# gpio_led.net
KiCad netlist of a schematic drawn in Altium Designer
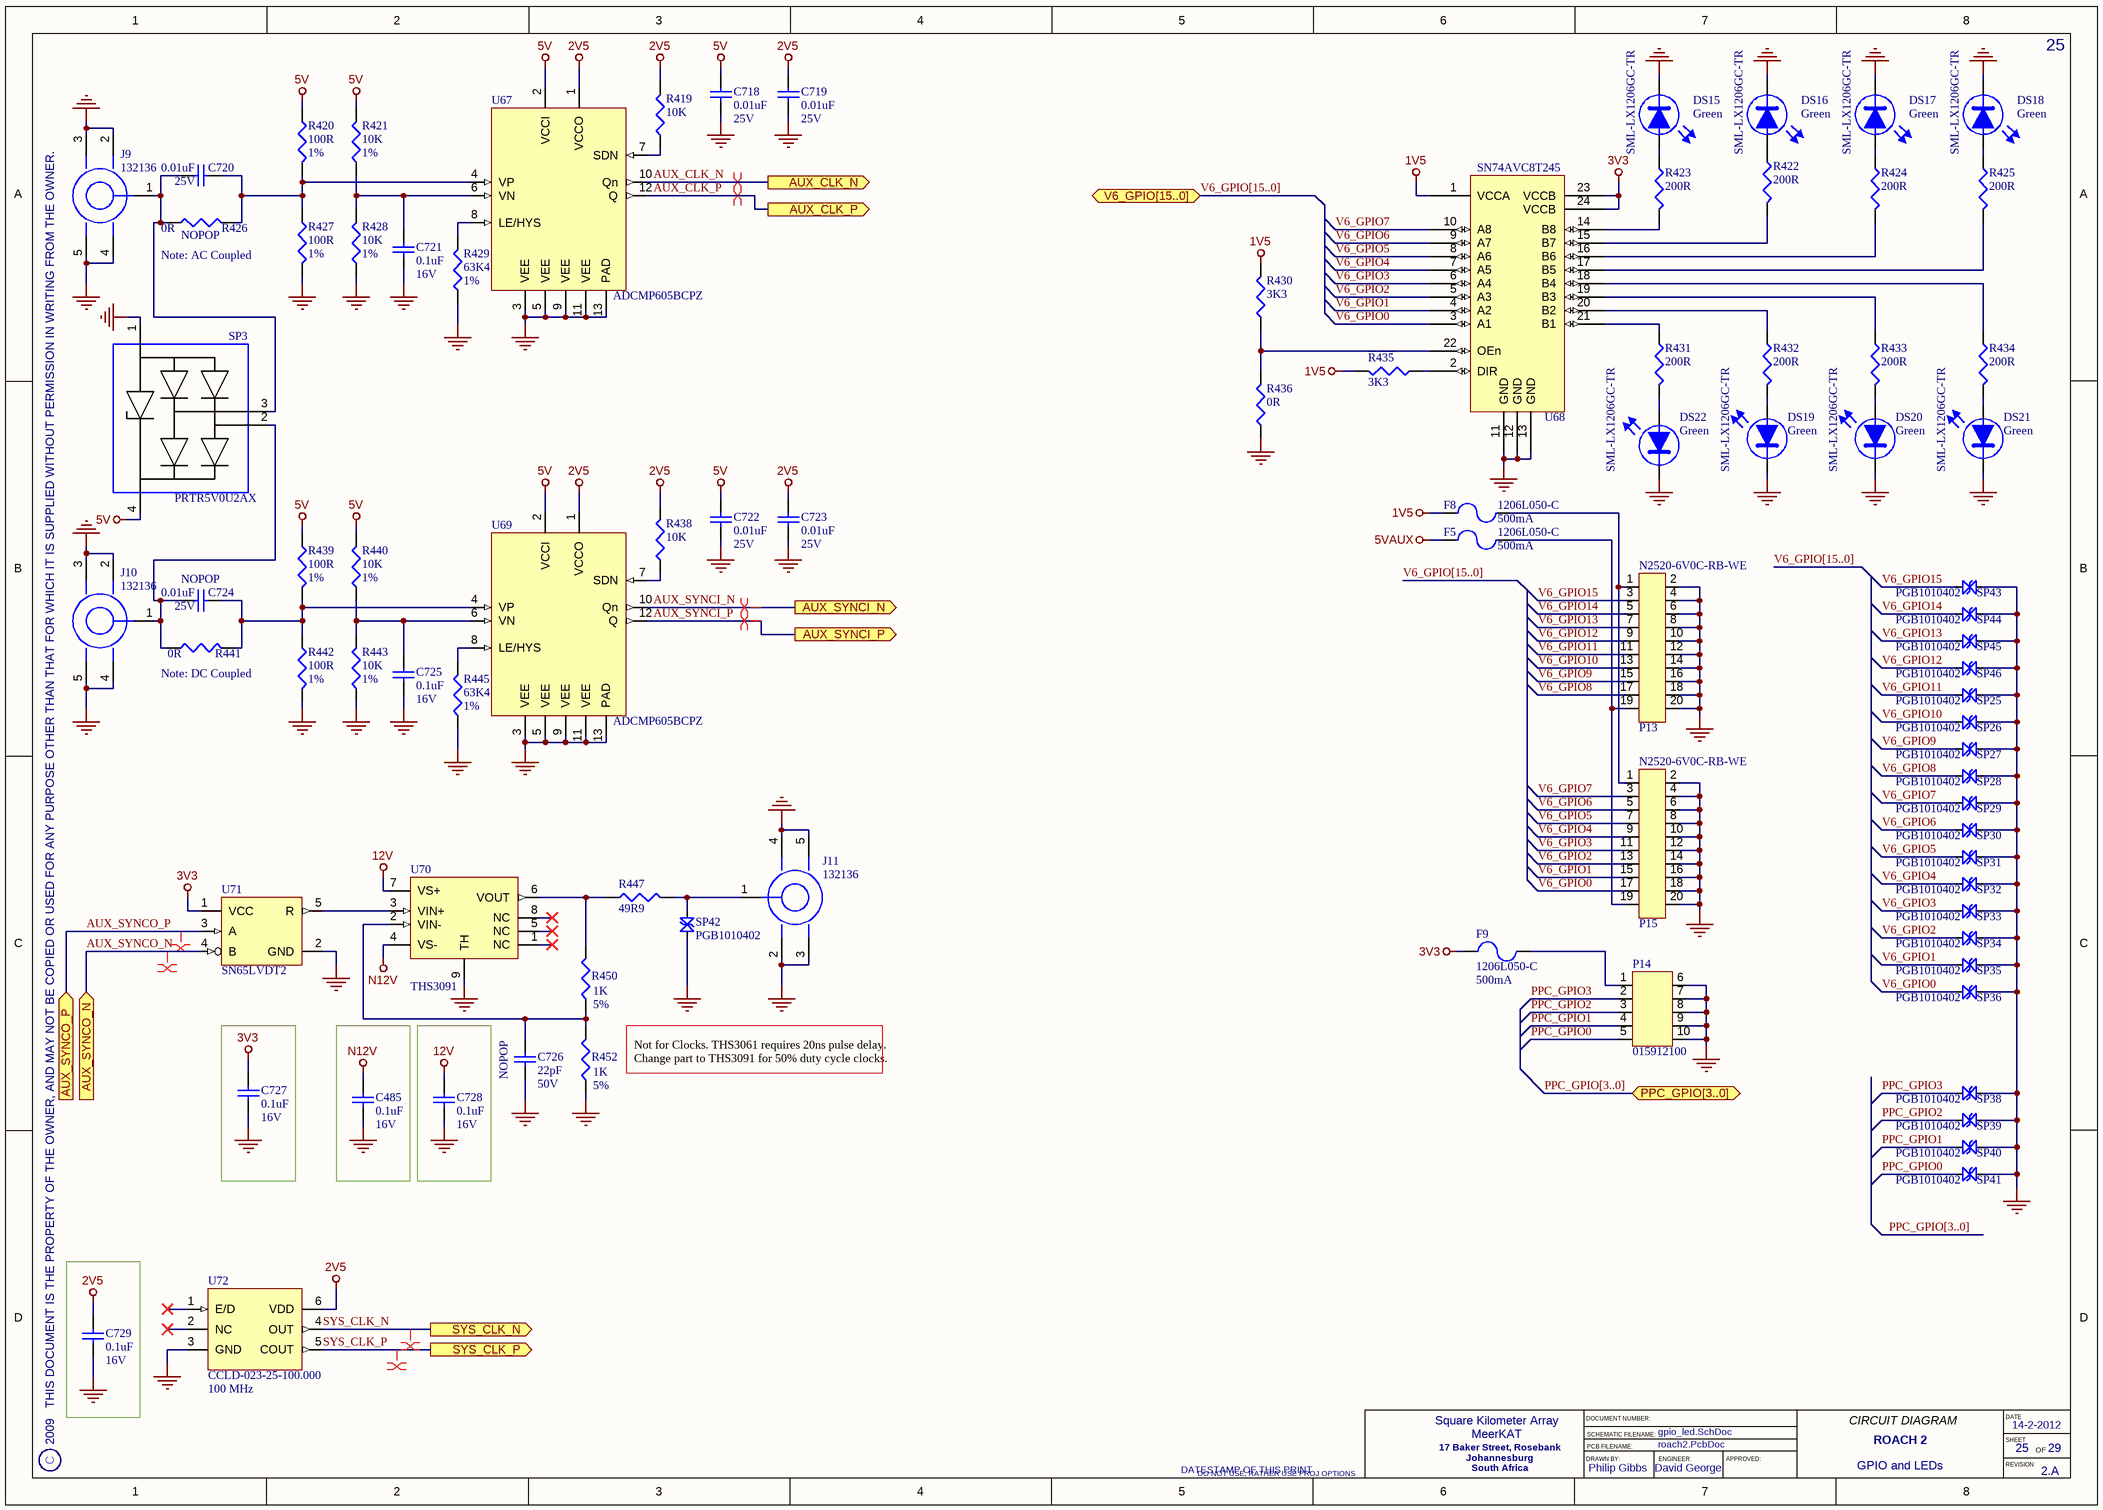
[diagram p0: gpio_led.SchDoc]

(export (version "E")
  (design (tool "Eeschema 10.0.6"))
  (components
    (comp (ref "C485")
      (value "0.1uF")
      (footprint "CAPC1005X60L")
      (description "0.1uF, Ceramic Capacitor")
      (fields
        (field (name "RATING") "16V")
        (field (name "MANUFACTURER") "VENKEL")
        (field (name "PARTNUM") "C0402X7R160-104KN")
      )
      (libsource (lib "altium_db") (part "CapStd"))
    )
    (comp (ref "C718")
      (value "0.01uF")
      (footprint "CAPC1005X55L")
      (description "0.01uF, Ceramic Capacitor")
      (fields
        (field (name "RATING") "25V")
        (field (name "MANUFACTURER") "MURATA")
        (field (name "PARTNUM") "GRM155R71E103KA01D")
      )
      (libsource (lib "altium_db") (part "CapStd"))
    )
    (comp (ref "C719")
      (value "0.01uF")
      (footprint "CAPC1005X55L")
      (description "0.01uF, Ceramic Capacitor")
      (fields
        (field (name "RATING") "25V")
        (field (name "MANUFACTURER") "MURATA")
        (field (name "PARTNUM") "GRM155R71E103KA01D")
      )
      (libsource (lib "altium_db") (part "CapStd"))
    )
    (comp (ref "C720")
      (value "0.01uF")
      (footprint "CAPC1005X55L")
      (description "0.01uF, Ceramic Capacitor")
      (fields
        (field (name "RATING") "25V")
        (field (name "MANUFACTURER") "MURATA")
        (field (name "PARTNUM") "GRM155R71E103KA01D")
      )
      (libsource (lib "altium_db") (part "CapStd"))
    )
    (comp (ref "C721")
      (value "0.1uF")
      (footprint "CAPC1005X60L")
      (description "0.1uF, Ceramic Capacitor")
      (fields
        (field (name "RATING") "16V")
        (field (name "MANUFACTURER") "VENKEL")
        (field (name "PARTNUM") "C0402X7R160-104KN")
      )
      (libsource (lib "altium_db") (part "CapStd"))
    )
    (comp (ref "C722")
      (value "0.01uF")
      (footprint "CAPC1005X55L")
      (description "0.01uF, Ceramic Capacitor")
      (fields
        (field (name "RATING") "25V")
        (field (name "MANUFACTURER") "MURATA")
        (field (name "PARTNUM") "GRM155R71E103KA01D")
      )
      (libsource (lib "altium_db") (part "CapStd"))
    )
    (comp (ref "C723")
      (value "0.01uF")
      (footprint "CAPC1005X55L")
      (description "0.01uF, Ceramic Capacitor")
      (fields
        (field (name "RATING") "25V")
        (field (name "MANUFACTURER") "MURATA")
        (field (name "PARTNUM") "GRM155R71E103KA01D")
      )
      (libsource (lib "altium_db") (part "CapStd"))
    )
    (comp (ref "C724")
      (value "0.01uF")
      (footprint "CAPC1005X55L")
      (description "0.01uF, Ceramic Capacitor")
      (fields
        (field (name "RATING") "25V")
        (field (name "MANUFACTURER") "MURATA")
        (field (name "PARTNUM") "GRM155R71E103KA01D")
      )
      (libsource (lib "altium_db") (part "CapStd"))
    )
    (comp (ref "C725")
      (value "0.1uF")
      (footprint "CAPC1005X60L")
      (description "0.1uF, Ceramic Capacitor")
      (fields
        (field (name "RATING") "16V")
        (field (name "MANUFACTURER") "VENKEL")
        (field (name "PARTNUM") "C0402X7R160-104KN")
      )
      (libsource (lib "altium_db") (part "CapStd"))
    )
    (comp (ref "C726")
      (value "22pF")
      (footprint "CAPC1005X55L")
      (description "22pF, Ceramic Capacitor")
      (fields
        (field (name "RATING") "50V")
        (field (name "MANUFACTURER") "MURATA")
        (field (name "PARTNUM") "GRM1555C1H220JZ01D")
      )
      (libsource (lib "altium_db") (part "CapStd"))
    )
    (comp (ref "C727")
      (value "0.1uF")
      (footprint "CAPC1005X60L")
      (description "0.1uF, Ceramic Capacitor")
      (fields
        (field (name "RATING") "16V")
        (field (name "MANUFACTURER") "VENKEL")
        (field (name "PARTNUM") "C0402X7R160-104KN")
      )
      (libsource (lib "altium_db") (part "CapStd"))
    )
    (comp (ref "C728")
      (value "0.1uF")
      (footprint "CAPC1005X60L")
      (description "0.1uF, Ceramic Capacitor")
      (fields
        (field (name "RATING") "16V")
        (field (name "MANUFACTURER") "VENKEL")
        (field (name "PARTNUM") "C0402X7R160-104KN")
      )
      (libsource (lib "altium_db") (part "CapStd"))
    )
    (comp (ref "C729")
      (value "0.1uF")
      (footprint "CAPC1005X60L")
      (description "0.1uF, Ceramic Capacitor")
      (fields
        (field (name "RATING") "16V")
        (field (name "MANUFACTURER") "VENKEL")
        (field (name "PARTNUM") "C0402X7R160-104KN")
      )
      (libsource (lib "altium_db") (part "CapStd"))
    )
    (comp (ref "DS15")
      (value "SML-LX1206GC-TR")
      (footprint "LEDC3216X120N")
      (description "Green, Surface mount, LED, 1206")
      (fields (field (name "COLOUR") "Green") (field (name "MANUFACTURER") "LUMEX"))
      (libsource (lib "altium_db") (part "LEDSTD"))
    )
    (comp (ref "DS16")
      (value "SML-LX1206GC-TR")
      (footprint "LEDC3216X120N")
      (description "Green, Surface mount, LED, 1206")
      (fields (field (name "COLOUR") "Green") (field (name "MANUFACTURER") "LUMEX"))
      (libsource (lib "altium_db") (part "LEDSTD"))
    )
    (comp (ref "DS17")
      (value "SML-LX1206GC-TR")
      (footprint "LEDC3216X120N")
      (description "Green, Surface mount, LED, 1206")
      (fields (field (name "COLOUR") "Green") (field (name "MANUFACTURER") "LUMEX"))
      (libsource (lib "altium_db") (part "LEDSTD"))
    )
    (comp (ref "DS18")
      (value "SML-LX1206GC-TR")
      (footprint "LEDC3216X120N")
      (description "Green, Surface mount, LED, 1206")
      (fields (field (name "COLOUR") "Green") (field (name "MANUFACTURER") "LUMEX"))
      (libsource (lib "altium_db") (part "LEDSTD"))
    )
    (comp (ref "DS19")
      (value "SML-LX1206GC-TR")
      (footprint "LEDC3216X120N")
      (description "Green, Surface mount, LED, 1206")
      (fields (field (name "COLOUR") "Green") (field (name "MANUFACTURER") "LUMEX"))
      (libsource (lib "altium_db") (part "LEDSTD"))
    )
    (comp (ref "DS20")
      (value "SML-LX1206GC-TR")
      (footprint "LEDC3216X120N")
      (description "Green, Surface mount, LED, 1206")
      (fields (field (name "COLOUR") "Green") (field (name "MANUFACTURER") "LUMEX"))
      (libsource (lib "altium_db") (part "LEDSTD"))
    )
    (comp (ref "DS21")
      (value "SML-LX1206GC-TR")
      (footprint "LEDC3216X120N")
      (description "Green, Surface mount, LED, 1206")
      (fields (field (name "COLOUR") "Green") (field (name "MANUFACTURER") "LUMEX"))
      (libsource (lib "altium_db") (part "LEDSTD"))
    )
    (comp (ref "DS22")
      (value "SML-LX1206GC-TR")
      (footprint "LEDC3216X120N")
      (description "Green, Surface mount, LED, 1206")
      (fields (field (name "COLOUR") "Green") (field (name "MANUFACTURER") "LUMEX"))
      (libsource (lib "altium_db") (part "LEDSTD"))
    )
    (comp (ref "F5")
      (value "1206L050-C")
      (footprint "FUSMC3215X145")
      (description "Resettable, Surface mount Fuse")
      (fields
        (field (name "PARTNUM") "1206L050-C")
        (field (name "MANUFACTURER") "Littelfuse")
        (field (name "RATING") "500mA")
      )
      (libsource (lib "altium_db") (part "FuseStd"))
    )
    (comp (ref "F8")
      (value "1206L050-C")
      (footprint "FUSMC3215X145")
      (description "Resettable, Surface mount Fuse")
      (fields
        (field (name "PARTNUM") "1206L050-C")
        (field (name "MANUFACTURER") "Littelfuse")
        (field (name "RATING") "500mA")
      )
      (libsource (lib "altium_db") (part "FuseStd"))
    )
    (comp (ref "F9")
      (value "1206L050-C")
      (footprint "FUSMC3215X145")
      (description "Resettable, Surface mount Fuse")
      (fields
        (field (name "PARTNUM") "1206L050-C")
        (field (name "MANUFACTURER") "Littelfuse")
        (field (name "RATING") "500mA")
      )
      (libsource (lib "altium_db") (part "FuseStd"))
    )
    (comp (ref "J9")
      (value "132136")
      (footprint "AMPHENOL_132134")
      (description "PCB-Mounted, Vertical, SMA Connector")
      (fields (field (name "PARTNUM") "132136") (field (name "MANUFACTURER") "Amphenol"))
      (libsource (lib "altium_db") (part "SMA_PCBMOUNT"))
    )
    (comp (ref "J10")
      (value "132136")
      (footprint "AMPHENOL_132134")
      (description "PCB-Mounted, Vertical, SMA Connector")
      (fields (field (name "PARTNUM") "132136") (field (name "MANUFACTURER") "Amphenol"))
      (libsource (lib "altium_db") (part "SMA_PCBMOUNT"))
    )
    (comp (ref "J11")
      (value "132136")
      (footprint "AMPHENOL_132134")
      (description "PCB-Mounted, Vertical, SMA Connector")
      (fields (field (name "PARTNUM") "132136") (field (name "MANUFACTURER") "Amphenol"))
      (libsource (lib "altium_db") (part "SMA_PCBMOUNT"))
    )
    (comp (ref "P13")
      (value "N2520-6V0C-RB-WE")
      (footprint "3M_N2520-6V0C-RB-WE")
      (description "2x10, 2.54mm Pitch, Male Shrouded Header")
      (fields (field (name "PARTNUM") "N2520-6V0C-RB-WE") (field (name "MANUFACTURER") "3M"))
      (libsource (lib "altium_db") (part "con_hdr_2x10_shr"))
    )
    (comp (ref "P14")
      (value "015912100")
      (footprint "MOLEX_0015912100")
      (description "2x5, 2.54 mm Pitch, Male Header")
      (fields (field (name "PARTNUM") "015912100") (field (name "MANUFACTURER") "Molex"))
      (libsource (lib "altium_db") (part "con_hdr_2x5"))
    )
    (comp (ref "P15")
      (value "N2520-6V0C-RB-WE")
      (footprint "3M_N2520-6V0C-RB-WE")
      (description "2x10, 2.54mm Pitch, Male Shrouded Header")
      (fields (field (name "PARTNUM") "N2520-6V0C-RB-WE") (field (name "MANUFACTURER") "3M"))
      (libsource (lib "altium_db") (part "con_hdr_2x10_shr"))
    )
    (comp (ref "R419")
      (value "10K")
      (footprint "RESC1005X40L")
      (description "10K, 1.1mm x 0.5mm, Thick Film Resistor")
      (fields (field (name "MANUFACTURER") "ROYALOHM") (field (name "PARTNUM") "0402WGJ0103T1E"))
      (libsource (lib "altium_db") (part "ResStd"))
    )
    (comp (ref "R420")
      (value "100R")
      (footprint "RESC1005X40L")
      (description "100R, 1.1mm x 0.5mm, Thick Film Resistor")
      (fields
        (field (name "MANUFACTURER") "ROYALOHM")
        (field (name "PARTNUM") "0402WGF0101T1E")
        (field (name "TOLERANCE") "1%")
      )
      (libsource (lib "altium_db") (part "ResStd"))
    )
    (comp (ref "R421")
      (value "10K")
      (footprint "RESC1005X40L")
      (description "10K, 1.1mm x 0.5mm, Thick Film Resistor")
      (fields
        (field (name "MANUFACTURER") "ROYALOHM")
        (field (name "PARTNUM") "0402WGF0103T1E")
        (field (name "TOLERANCE") "1%")
      )
      (libsource (lib "altium_db") (part "ResStd"))
    )
    (comp (ref "R422")
      (value "200R")
      (footprint "RESC1005X40L")
      (description "200R, 1.1mm x 0.5mm, Thick Film Resistor")
      (fields (field (name "MANUFACTURER") "ROYALOHM") (field (name "PARTNUM") "0402WGF0201T1E"))
      (libsource (lib "altium_db") (part "ResStd"))
    )
    (comp (ref "R423")
      (value "200R")
      (footprint "RESC1005X40L")
      (description "200R, 1.1mm x 0.5mm, Thick Film Resistor")
      (fields (field (name "MANUFACTURER") "ROYALOHM") (field (name "PARTNUM") "0402WGF0201T1E"))
      (libsource (lib "altium_db") (part "ResStd"))
    )
    (comp (ref "R424")
      (value "200R")
      (footprint "RESC1005X40L")
      (description "200R, 1.1mm x 0.5mm, Thick Film Resistor")
      (fields (field (name "MANUFACTURER") "ROYALOHM") (field (name "PARTNUM") "0402WGF0201T1E"))
      (libsource (lib "altium_db") (part "ResStd"))
    )
    (comp (ref "R425")
      (value "200R")
      (footprint "RESC1005X40L")
      (description "200R, 1.1mm x 0.5mm, Thick Film Resistor")
      (fields (field (name "MANUFACTURER") "ROYALOHM") (field (name "PARTNUM") "0402WGF0201T1E"))
      (libsource (lib "altium_db") (part "ResStd"))
    )
    (comp (ref "R426")
      (value "0R")
      (footprint "RESC1005X40L")
      (description "0R, 1.1mm x 0.5mm, Thick Film Resistor")
      (fields (field (name "MANUFACTURER") "ROYALOHM") (field (name "PARTNUM") "0402WG00000T1E"))
      (libsource (lib "altium_db") (part "ResStd"))
    )
    (comp (ref "R427")
      (value "100R")
      (footprint "RESC1005X40L")
      (description "100R, 1.1mm x 0.5mm, Thick Film Resistor")
      (fields
        (field (name "MANUFACTURER") "ROYALOHM")
        (field (name "PARTNUM") "0402WGF0101T1E")
        (field (name "TOLERANCE") "1%")
      )
      (libsource (lib "altium_db") (part "ResStd"))
    )
    (comp (ref "R428")
      (value "10K")
      (footprint "RESC1005X40L")
      (description "10K, 1.1mm x 0.5mm, Thick Film Resistor")
      (fields
        (field (name "MANUFACTURER") "ROYALOHM")
        (field (name "PARTNUM") "0402WGF0103T1E")
        (field (name "TOLERANCE") "1%")
      )
      (libsource (lib "altium_db") (part "ResStd"))
    )
    (comp (ref "R429")
      (value "63K4")
      (footprint "RESC1005X40L")
      (description "63K4, 1.1mm x 0.5mm, Thick Film Resistor")
      (fields
        (field (name "MANUFACTURER") "ROYALOHM")
        (field (name "PARTNUM") "0402WGF6342T1E")
        (field (name "TOLERANCE") "1%")
      )
      (libsource (lib "altium_db") (part "ResStd"))
    )
    (comp (ref "R430")
      (value "3K3")
      (footprint "RESC1005X40L")
      (description "3K3, 1.1mm x 0.5mm, Thick Film Resistor")
      (fields (field (name "MANUFACTURER") "ROYALOHM") (field (name "PARTNUM") "0402WGJ0332T1E"))
      (libsource (lib "altium_db") (part "ResStd"))
    )
    (comp (ref "R431")
      (value "200R")
      (footprint "RESC1005X40L")
      (description "200R, 1.1mm x 0.5mm, Thick Film Resistor")
      (fields (field (name "MANUFACTURER") "ROYALOHM") (field (name "PARTNUM") "0402WGF0201T1E"))
      (libsource (lib "altium_db") (part "ResStd"))
    )
    (comp (ref "R432")
      (value "200R")
      (footprint "RESC1005X40L")
      (description "200R, 1.1mm x 0.5mm, Thick Film Resistor")
      (fields (field (name "MANUFACTURER") "ROYALOHM") (field (name "PARTNUM") "0402WGF0201T1E"))
      (libsource (lib "altium_db") (part "ResStd"))
    )
    (comp (ref "R433")
      (value "200R")
      (footprint "RESC1005X40L")
      (description "200R, 1.1mm x 0.5mm, Thick Film Resistor")
      (fields (field (name "MANUFACTURER") "ROYALOHM") (field (name "PARTNUM") "0402WGF0201T1E"))
      (libsource (lib "altium_db") (part "ResStd"))
    )
    (comp (ref "R434")
      (value "200R")
      (footprint "RESC1005X40L")
      (description "200R, 1.1mm x 0.5mm, Thick Film Resistor")
      (fields (field (name "MANUFACTURER") "ROYALOHM") (field (name "PARTNUM") "0402WGF0201T1E"))
      (libsource (lib "altium_db") (part "ResStd"))
    )
    (comp (ref "R435")
      (value "3K3")
      (footprint "RESC1005X40L")
      (description "3K3, 1.1mm x 0.5mm, Thick Film Resistor")
      (fields (field (name "MANUFACTURER") "ROYALOHM") (field (name "PARTNUM") "0402WGJ0332T1E"))
      (libsource (lib "altium_db") (part "ResStd"))
    )
    (comp (ref "R436")
      (value "0R")
      (footprint "RESC1005X40L")
      (description "0R, 1.1mm x 0.5mm, Thick Film Resistor")
      (fields (field (name "MANUFACTURER") "ROYALOHM") (field (name "PARTNUM") "0402WG00000T1E"))
      (libsource (lib "altium_db") (part "ResStd"))
    )
    (comp (ref "R438")
      (value "10K")
      (footprint "RESC1005X40L")
      (description "10K, 1.1mm x 0.5mm, Thick Film Resistor")
      (fields (field (name "MANUFACTURER") "ROYALOHM") (field (name "PARTNUM") "0402WGJ0103T1E"))
      (libsource (lib "altium_db") (part "ResStd"))
    )
    (comp (ref "R439")
      (value "100R")
      (footprint "RESC1005X40L")
      (description "100R, 1.1mm x 0.5mm, Thick Film Resistor")
      (fields
        (field (name "MANUFACTURER") "ROYALOHM")
        (field (name "PARTNUM") "0402WGF0101T1E")
        (field (name "TOLERANCE") "1%")
      )
      (libsource (lib "altium_db") (part "ResStd"))
    )
    (comp (ref "R440")
      (value "10K")
      (footprint "RESC1005X40L")
      (description "10K, 1.1mm x 0.5mm, Thick Film Resistor")
      (fields
        (field (name "MANUFACTURER") "ROYALOHM")
        (field (name "PARTNUM") "0402WGF0103T1E")
        (field (name "TOLERANCE") "1%")
      )
      (libsource (lib "altium_db") (part "ResStd"))
    )
    (comp (ref "R441")
      (value "0R")
      (footprint "RESC1005X40L")
      (description "0R, 1.1mm x 0.5mm, Thick Film Resistor")
      (fields (field (name "MANUFACTURER") "ROYALOHM") (field (name "PARTNUM") "0402WG00000T1E"))
      (libsource (lib "altium_db") (part "ResStd"))
    )
    (comp (ref "R442")
      (value "100R")
      (footprint "RESC1005X40L")
      (description "100R, 1.1mm x 0.5mm, Thick Film Resistor")
      (fields
        (field (name "MANUFACTURER") "ROYALOHM")
        (field (name "PARTNUM") "0402WGF0101T1E")
        (field (name "TOLERANCE") "1%")
      )
      (libsource (lib "altium_db") (part "ResStd"))
    )
    (comp (ref "R443")
      (value "10K")
      (footprint "RESC1005X40L")
      (description "10K, 1.1mm x 0.5mm, Thick Film Resistor")
      (fields
        (field (name "MANUFACTURER") "ROYALOHM")
        (field (name "PARTNUM") "0402WGF0103T1E")
        (field (name "TOLERANCE") "1%")
      )
      (libsource (lib "altium_db") (part "ResStd"))
    )
    (comp (ref "R445")
      (value "63K4")
      (footprint "RESC1005X40L")
      (description "63K4, 1.1mm x 0.5mm, Thick Film Resistor")
      (fields
        (field (name "MANUFACTURER") "ROYALOHM")
        (field (name "PARTNUM") "0402WGF6342T1E")
        (field (name "TOLERANCE") "1%")
      )
      (libsource (lib "altium_db") (part "ResStd"))
    )
    (comp (ref "R447")
      (value "49R9")
      (footprint "RESC1005X40L")
      (description "49R9, 1.1mm x 0.5mm, Thick Film Resistor")
      (fields (field (name "MANUFACTURER") "ROYALOHM") (field (name "PARTNUM") "0402WGF499JT1E"))
      (libsource (lib "altium_db") (part "ResStd"))
    )
    (comp (ref "R450")
      (value "1K")
      (footprint "RESC1005X40L")
      (description "1K, 1.1mm x 0.5mm, Thick Film Resistor")
      (fields
        (field (name "MANUFACTURER") "ROYALOHM")
        (field (name "PARTNUM") "0402WGJ0102T1E")
        (field (name "TOLERANCE") "5%")
      )
      (libsource (lib "altium_db") (part "ResStd"))
    )
    (comp (ref "R452")
      (value "1K")
      (footprint "RESC1005X40L")
      (description "1K, 1.1mm x 0.5mm, Thick Film Resistor")
      (fields
        (field (name "MANUFACTURER") "ROYALOHM")
        (field (name "PARTNUM") "0402WGJ0102T1E")
        (field (name "TOLERANCE") "5%")
      )
      (libsource (lib "altium_db") (part "ResStd"))
    )
    (comp (ref "SP3")
      (value "PRTR5V0U2AX")
      (footprint "SOT192P237X120-4N")
      (description "Ultra-low capacitance, double rail-to-rail, ESD protection diode in a SOT143B package")
      (fields (field (name "PARTNUM") "PRTR5V0U2AX") (field (name "MANUFACTURER") "NXP"))
      (libsource (lib "altium_db") (part "PRTR5V0U2AX"))
    )
    (comp (ref "SP25")
      (value "PGB1010402")
      (footprint "PGB1010402")
      (description "Surface Mount Polymeric ESD Suppressor in an 0402 package")
      (fields (field (name "PARTNUM") "PGB1010402"))
      (libsource (lib "altium_db") (part "PGB1010402"))
    )
    (comp (ref "SP26")
      (value "PGB1010402")
      (footprint "PGB1010402")
      (description "Surface Mount Polymeric ESD Suppressor in an 0402 package")
      (fields (field (name "PARTNUM") "PGB1010402"))
      (libsource (lib "altium_db") (part "PGB1010402"))
    )
    (comp (ref "SP27")
      (value "PGB1010402")
      (footprint "PGB1010402")
      (description "Surface Mount Polymeric ESD Suppressor in an 0402 package")
      (fields (field (name "PARTNUM") "PGB1010402"))
      (libsource (lib "altium_db") (part "PGB1010402"))
    )
    (comp (ref "SP28")
      (value "PGB1010402")
      (footprint "PGB1010402")
      (description "Surface Mount Polymeric ESD Suppressor in an 0402 package")
      (fields (field (name "PARTNUM") "PGB1010402"))
      (libsource (lib "altium_db") (part "PGB1010402"))
    )
    (comp (ref "SP29")
      (value "PGB1010402")
      (footprint "PGB1010402")
      (description "Surface Mount Polymeric ESD Suppressor in an 0402 package")
      (fields (field (name "PARTNUM") "PGB1010402"))
      (libsource (lib "altium_db") (part "PGB1010402"))
    )
    (comp (ref "SP30")
      (value "PGB1010402")
      (footprint "PGB1010402")
      (description "Surface Mount Polymeric ESD Suppressor in an 0402 package")
      (fields (field (name "PARTNUM") "PGB1010402"))
      (libsource (lib "altium_db") (part "PGB1010402"))
    )
    (comp (ref "SP31")
      (value "PGB1010402")
      (footprint "PGB1010402")
      (description "Surface Mount Polymeric ESD Suppressor in an 0402 package")
      (fields (field (name "PARTNUM") "PGB1010402"))
      (libsource (lib "altium_db") (part "PGB1010402"))
    )
    (comp (ref "SP32")
      (value "PGB1010402")
      (footprint "PGB1010402")
      (description "Surface Mount Polymeric ESD Suppressor in an 0402 package")
      (fields (field (name "PARTNUM") "PGB1010402"))
      (libsource (lib "altium_db") (part "PGB1010402"))
    )
    (comp (ref "SP33")
      (value "PGB1010402")
      (footprint "PGB1010402")
      (description "Surface Mount Polymeric ESD Suppressor in an 0402 package")
      (fields (field (name "PARTNUM") "PGB1010402"))
      (libsource (lib "altium_db") (part "PGB1010402"))
    )
    (comp (ref "SP34")
      (value "PGB1010402")
      (footprint "PGB1010402")
      (description "Surface Mount Polymeric ESD Suppressor in an 0402 package")
      (fields (field (name "PARTNUM") "PGB1010402"))
      (libsource (lib "altium_db") (part "PGB1010402"))
    )
    (comp (ref "SP35")
      (value "PGB1010402")
      (footprint "PGB1010402")
      (description "Surface Mount Polymeric ESD Suppressor in an 0402 package")
      (fields (field (name "PARTNUM") "PGB1010402"))
      (libsource (lib "altium_db") (part "PGB1010402"))
    )
    (comp (ref "SP36")
      (value "PGB1010402")
      (footprint "PGB1010402")
      (description "Surface Mount Polymeric ESD Suppressor in an 0402 package")
      (fields (field (name "PARTNUM") "PGB1010402"))
      (libsource (lib "altium_db") (part "PGB1010402"))
    )
    (comp (ref "SP38")
      (value "PGB1010402")
      (footprint "PGB1010402")
      (description "Surface Mount Polymeric ESD Suppressor in an 0402 package")
      (fields (field (name "PARTNUM") "PGB1010402"))
      (libsource (lib "altium_db") (part "PGB1010402"))
    )
    (comp (ref "SP39")
      (value "PGB1010402")
      (footprint "PGB1010402")
      (description "Surface Mount Polymeric ESD Suppressor in an 0402 package")
      (fields (field (name "PARTNUM") "PGB1010402"))
      (libsource (lib "altium_db") (part "PGB1010402"))
    )
    (comp (ref "SP40")
      (value "PGB1010402")
      (footprint "PGB1010402")
      (description "Surface Mount Polymeric ESD Suppressor in an 0402 package")
      (fields (field (name "PARTNUM") "PGB1010402"))
      (libsource (lib "altium_db") (part "PGB1010402"))
    )
    (comp (ref "SP41")
      (value "PGB1010402")
      (footprint "PGB1010402")
      (description "Surface Mount Polymeric ESD Suppressor in an 0402 package")
      (fields (field (name "PARTNUM") "PGB1010402"))
      (libsource (lib "altium_db") (part "PGB1010402"))
    )
    (comp (ref "SP42")
      (value "PGB1010402")
      (footprint "PGB1010402")
      (description "Surface Mount Polymeric ESD Suppressor in an 0402 package")
      (fields (field (name "PARTNUM") "PGB1010402"))
      (libsource (lib "altium_db") (part "PGB1010402"))
    )
    (comp (ref "SP43")
      (value "PGB1010402")
      (footprint "PGB1010402")
      (description "Surface Mount Polymeric ESD Suppressor in an 0402 package")
      (fields (field (name "PARTNUM") "PGB1010402"))
      (libsource (lib "altium_db") (part "PGB1010402"))
    )
    (comp (ref "SP44")
      (value "PGB1010402")
      (footprint "PGB1010402")
      (description "Surface Mount Polymeric ESD Suppressor in an 0402 package")
      (fields (field (name "PARTNUM") "PGB1010402"))
      (libsource (lib "altium_db") (part "PGB1010402"))
    )
    (comp (ref "SP45")
      (value "PGB1010402")
      (footprint "PGB1010402")
      (description "Surface Mount Polymeric ESD Suppressor in an 0402 package")
      (fields (field (name "PARTNUM") "PGB1010402"))
      (libsource (lib "altium_db") (part "PGB1010402"))
    )
    (comp (ref "SP46")
      (value "PGB1010402")
      (footprint "PGB1010402")
      (description "Surface Mount Polymeric ESD Suppressor in an 0402 package")
      (fields (field (name "PARTNUM") "PGB1010402"))
      (libsource (lib "altium_db") (part "PGB1010402"))
    )
    (comp (ref "U67")
      (value "ADCMP605BCPZ")
      (footprint "LFCSP_VQ-12")
      (description "Rail-to-Rail, Very Fast, 2.5 V to 5.5 V, Single-Supply LVDS Comparators")
      (fields (field (name "MANUFACTURER") "Analog Devices"))
      (libsource (lib "altium_db") (part "ADCMP605"))
    )
    (comp (ref "U68")
      (value "SN74AVC8T245")
      (footprint "PW024")
      (description "8-BIT DUAL-SUPPLY BUS TRANSCEIVER  WITH CONFIGURABLE VOLTAGE TRANSLATION AND 3-STATE OUTPUTS")
      (fields (field (name "MANUFACTURER") "Texas Instruments"))
      (libsource (lib "altium_db") (part "SN74AVC8T245"))
    )
    (comp (ref "U69")
      (value "ADCMP605BCPZ")
      (footprint "LFCSP_VQ-12")
      (description "Rail-to-Rail, Very Fast, 2.5 V to 5.5 V, Single-Supply LVDS Comparators")
      (fields (field (name "MANUFACTURER") "Analog Devices"))
      (libsource (lib "altium_db") (part "ADCMP605"))
    )
    (comp (ref "U70")
      (value "THS3091")
      (footprint "SOIC8-PP")
      (description "HIGH VOLTAGE, LOW-DISTORTION, CURRENT-FEEDBACK AMPLIFIERS")
      (fields (field (name "MANUFACTURER") "Texas Instruments") (field (name "PARTNUM") "THS3091DDA"))
      (libsource (lib "Altium_DB") (part "THS3091"))
    )
    (comp (ref "U71")
      (value "SN65LVDT2")
      (footprint "SOT23-5")
      (description "Single High-Speed Differential Line Receiver with ODT")
      (fields (field (name "MANUFACTURER") "Texas Instruments"))
      (libsource (lib "altium_db") (part "SN65LVDT2"))
    )
    (comp (ref "U72")
      (value "CCLD-023-25-100.000")
      (footprint "CCLD-023X-XX-XXX_XXX")
      (description "100.00 MHz, Low-Jitter Differential LVDS Clock Oscillator")
      (fields
        (field (name "PARTNUM") "CCLD-023-25-100.000")
        (field (name "FREQUENCY") "100 MHz")
        (field (name "MANUFACTURER") "Crystek")
      )
      (libsource (lib "altium_db") (part "CCLD-023X-XX-XXX_XXX"))
    )
  )
  (nets
    (net (code "1") (name "/AUX_CLK_N") (class "Default")
      (node (ref "U67") (pin "10") (pinfunction "Qn_10") (pintype "output"))
    )
    (net (code "2") (name "/AUX_CLK_P") (class "Default")
      (node (ref "U67") (pin "12") (pinfunction "Q_12") (pintype "output"))
    )
    (net (code "3") (name "/AUX_SYNCI_N") (class "Default")
      (node (ref "U69") (pin "10") (pinfunction "Qn_10") (pintype "output"))
    )
    (net (code "4") (name "/AUX_SYNCI_P") (class "Default")
      (node (ref "U69") (pin "12") (pinfunction "Q_12") (pintype "output"))
    )
    (net (code "5") (name "/AUX_SYNCO_N") (class "Default")
      (node (ref "U71") (pin "4") (pinfunction "B_4") (pintype "input"))
    )
    (net (code "6") (name "/AUX_SYNCO_P") (class "Default")
      (node (ref "U71") (pin "3") (pinfunction "A_3") (pintype "input"))
    )
    (net (code "7") (name "/PPC_GPIO0") (class "Default")
      (node (ref "P14") (pin "5") (pinfunction "5_5") (pintype "passive"))
      (node (ref "SP41") (pin "2") (pinfunction "B_2") (pintype "passive"))
    )
    (net (code "8") (name "/PPC_GPIO1") (class "Default")
      (node (ref "P14") (pin "4") (pinfunction "4_4") (pintype "passive"))
      (node (ref "SP40") (pin "2") (pinfunction "B_2") (pintype "passive"))
    )
    (net (code "9") (name "/PPC_GPIO2") (class "Default")
      (node (ref "P14") (pin "3") (pinfunction "3_3") (pintype "passive"))
      (node (ref "SP39") (pin "2") (pinfunction "B_2") (pintype "passive"))
    )
    (net (code "10") (name "/PPC_GPIO3") (class "Default")
      (node (ref "P14") (pin "2") (pinfunction "2_2") (pintype "passive"))
      (node (ref "SP38") (pin "2") (pinfunction "B_2") (pintype "passive"))
    )
    (net (code "12") (name "/SYS_CLK_N") (class "Default")
      (node (ref "U72") (pin "4") (pinfunction "OUT_4") (pintype "output"))
    )
    (net (code "13") (name "/SYS_CLK_P") (class "Default")
      (node (ref "U72") (pin "5") (pinfunction "COUT_5") (pintype "output"))
    )
    (net (code "14") (name "/V6_GPIO0") (class "Default")
      (node (ref "P15") (pin "17") (pinfunction "17_17") (pintype "passive"))
      (node (ref "SP36") (pin "2") (pinfunction "B_2") (pintype "passive"))
      (node (ref "U68") (pin "3") (pinfunction "A1_3") (pintype "bidirectional"))
    )
    (net (code "15") (name "/V6_GPIO1") (class "Default")
      (node (ref "P15") (pin "15") (pinfunction "15_15") (pintype "passive"))
      (node (ref "SP35") (pin "2") (pinfunction "B_2") (pintype "passive"))
      (node (ref "U68") (pin "4") (pinfunction "A2_4") (pintype "bidirectional"))
    )
    (net (code "16") (name "/V6_GPIO2") (class "Default")
      (node (ref "P15") (pin "13") (pinfunction "13_13") (pintype "passive"))
      (node (ref "SP34") (pin "2") (pinfunction "B_2") (pintype "passive"))
      (node (ref "U68") (pin "5") (pinfunction "A3_5") (pintype "bidirectional"))
    )
    (net (code "17") (name "/V6_GPIO3") (class "Default")
      (node (ref "P15") (pin "11") (pinfunction "11_11") (pintype "passive"))
      (node (ref "SP33") (pin "2") (pinfunction "B_2") (pintype "passive"))
      (node (ref "U68") (pin "6") (pinfunction "A4_6") (pintype "bidirectional"))
    )
    (net (code "18") (name "/V6_GPIO4") (class "Default")
      (node (ref "P15") (pin "9") (pinfunction "9_9") (pintype "passive"))
      (node (ref "SP32") (pin "2") (pinfunction "B_2") (pintype "passive"))
      (node (ref "U68") (pin "7") (pinfunction "A5_7") (pintype "bidirectional"))
    )
    (net (code "19") (name "/V6_GPIO5") (class "Default")
      (node (ref "P15") (pin "7") (pinfunction "7_7") (pintype "passive"))
      (node (ref "SP31") (pin "2") (pinfunction "B_2") (pintype "passive"))
      (node (ref "U68") (pin "8") (pinfunction "A6_8") (pintype "bidirectional"))
    )
    (net (code "20") (name "/V6_GPIO6") (class "Default")
      (node (ref "P15") (pin "5") (pinfunction "5_5") (pintype "passive"))
      (node (ref "SP30") (pin "2") (pinfunction "B_2") (pintype "passive"))
      (node (ref "U68") (pin "9") (pinfunction "A7_9") (pintype "bidirectional"))
    )
    (net (code "21") (name "/V6_GPIO7") (class "Default")
      (node (ref "P15") (pin "3") (pinfunction "3_3") (pintype "passive"))
      (node (ref "SP29") (pin "2") (pinfunction "B_2") (pintype "passive"))
      (node (ref "U68") (pin "10") (pinfunction "A8_10") (pintype "bidirectional"))
    )
    (net (code "22") (name "/V6_GPIO8") (class "Default")
      (node (ref "P13") (pin "17") (pinfunction "17_17") (pintype "passive"))
      (node (ref "SP28") (pin "2") (pinfunction "B_2") (pintype "passive"))
    )
    (net (code "23") (name "/V6_GPIO9") (class "Default")
      (node (ref "P13") (pin "15") (pinfunction "15_15") (pintype "passive"))
      (node (ref "SP27") (pin "2") (pinfunction "B_2") (pintype "passive"))
    )
    (net (code "24") (name "/V6_GPIO10") (class "Default")
      (node (ref "P13") (pin "13") (pinfunction "13_13") (pintype "passive"))
      (node (ref "SP26") (pin "2") (pinfunction "B_2") (pintype "passive"))
    )
    (net (code "25") (name "/V6_GPIO11") (class "Default")
      (node (ref "P13") (pin "11") (pinfunction "11_11") (pintype "passive"))
      (node (ref "SP25") (pin "2") (pinfunction "B_2") (pintype "passive"))
    )
    (net (code "26") (name "/V6_GPIO12") (class "Default")
      (node (ref "P13") (pin "9") (pinfunction "9_9") (pintype "passive"))
      (node (ref "SP46") (pin "2") (pinfunction "B_2") (pintype "passive"))
    )
    (net (code "27") (name "/V6_GPIO13") (class "Default")
      (node (ref "P13") (pin "7") (pinfunction "7_7") (pintype "passive"))
      (node (ref "SP45") (pin "2") (pinfunction "B_2") (pintype "passive"))
    )
    (net (code "28") (name "/V6_GPIO14") (class "Default")
      (node (ref "P13") (pin "5") (pinfunction "5_5") (pintype "passive"))
      (node (ref "SP44") (pin "2") (pinfunction "B_2") (pintype "passive"))
    )
    (net (code "29") (name "/V6_GPIO15") (class "Default")
      (node (ref "P13") (pin "3") (pinfunction "3_3") (pintype "passive"))
      (node (ref "SP43") (pin "2") (pinfunction "B_2") (pintype "passive"))
    )
    (net (code "31") (name "1V5") (class "Default")
      (node (ref "F8") (pin "1") (pinfunction "1_1") (pintype "passive"))
      (node (ref "R430") (pin "2") (pinfunction "2_2") (pintype "passive"))
      (node (ref "R435") (pin "2") (pinfunction "2_2") (pintype "passive"))
      (node (ref "U68") (pin "1") (pinfunction "VCCA_1") (pintype "power_in"))
    )
    (net (code "32") (name "2V5") (class "Default")
      (node (ref "C719") (pin "2") (pinfunction "2_2") (pintype "passive"))
      (node (ref "C723") (pin "2") (pinfunction "2_2") (pintype "passive"))
      (node (ref "C729") (pin "2") (pinfunction "2_2") (pintype "passive"))
      (node (ref "R419") (pin "2") (pinfunction "2_2") (pintype "passive"))
      (node (ref "R438") (pin "2") (pinfunction "2_2") (pintype "passive"))
      (node (ref "U67") (pin "1") (pinfunction "VCCO_1") (pintype "power_in"))
      (node (ref "U69") (pin "1") (pinfunction "VCCO_1") (pintype "power_in"))
      (node (ref "U72") (pin "6") (pinfunction "VDD_6") (pintype "power_in"))
    )
    (net (code "33") (name "3V3") (class "Default")
      (node (ref "C727") (pin "2") (pinfunction "2_2") (pintype "passive"))
      (node (ref "F9") (pin "2") (pinfunction "2_2") (pintype "passive"))
      (node (ref "U68") (pin "23") (pinfunction "VCCB_23") (pintype "power_in"))
      (node (ref "U68") (pin "24") (pinfunction "VCCB_24") (pintype "power_in"))
      (node (ref "U71") (pin "1") (pinfunction "VCC_1") (pintype "power_in"))
    )
    (net (code "34") (name "5V") (class "Default")
      (node (ref "C718") (pin "2") (pinfunction "2_2") (pintype "passive"))
      (node (ref "C722") (pin "2") (pinfunction "2_2") (pintype "passive"))
      (node (ref "R420") (pin "1") (pinfunction "1_1") (pintype "passive"))
      (node (ref "R421") (pin "2") (pinfunction "2_2") (pintype "passive"))
      (node (ref "R439") (pin "1") (pinfunction "1_1") (pintype "passive"))
      (node (ref "R440") (pin "2") (pinfunction "2_2") (pintype "passive"))
      (node (ref "SP3") (pin "4") (pinfunction "VCC_4") (pintype "power_in"))
      (node (ref "U67") (pin "2") (pinfunction "VCCI_2") (pintype "power_in"))
      (node (ref "U69") (pin "2") (pinfunction "VCCI_2") (pintype "power_in"))
    )
    (net (code "35") (name "5VAUX") (class "Default")
      (node (ref "F5") (pin "1") (pinfunction "1_1") (pintype "passive"))
    )
    (net (code "36") (name "12V") (class "Default")
      (node (ref "C728") (pin "2") (pinfunction "2_2") (pintype "passive"))
      (node (ref "U70") (pin "7") (pinfunction "VS+_7") (pintype "power_in"))
    )
    (net (code "37") (name "GND") (class "Default")
      (node (ref "C485") (pin "1") (pinfunction "1_1") (pintype "passive"))
      (node (ref "C718") (pin "1") (pinfunction "1_1") (pintype "passive"))
      (node (ref "C719") (pin "1") (pinfunction "1_1") (pintype "passive"))
      (node (ref "C721") (pin "1") (pinfunction "1_1") (pintype "passive"))
      (node (ref "C722") (pin "1") (pinfunction "1_1") (pintype "passive"))
      (node (ref "C723") (pin "1") (pinfunction "1_1") (pintype "passive"))
      (node (ref "C725") (pin "1") (pinfunction "1_1") (pintype "passive"))
      (node (ref "C726") (pin "1") (pinfunction "1_1") (pintype "passive"))
      (node (ref "C727") (pin "1") (pinfunction "1_1") (pintype "passive"))
      (node (ref "C728") (pin "1") (pinfunction "1_1") (pintype "passive"))
      (node (ref "C729") (pin "1") (pinfunction "1_1") (pintype "passive"))
      (node (ref "DS15") (pin "1") (pinfunction "K_1") (pintype "passive"))
      (node (ref "DS16") (pin "1") (pinfunction "K_1") (pintype "passive"))
      (node (ref "DS17") (pin "1") (pinfunction "K_1") (pintype "passive"))
      (node (ref "DS18") (pin "1") (pinfunction "K_1") (pintype "passive"))
      (node (ref "DS19") (pin "1") (pinfunction "K_1") (pintype "passive"))
      (node (ref "DS20") (pin "1") (pinfunction "K_1") (pintype "passive"))
      (node (ref "DS21") (pin "1") (pinfunction "K_1") (pintype "passive"))
      (node (ref "DS22") (pin "1") (pinfunction "K_1") (pintype "passive"))
      (node (ref "J10") (pin "2") (pinfunction "SH_2") (pintype "passive"))
      (node (ref "J10") (pin "3") (pinfunction "SH_3") (pintype "passive"))
      (node (ref "J10") (pin "4") (pinfunction "SH_4") (pintype "passive"))
      (node (ref "J10") (pin "5") (pinfunction "SH_5") (pintype "passive"))
      (node (ref "J11") (pin "2") (pinfunction "SH_2") (pintype "passive"))
      (node (ref "J11") (pin "3") (pinfunction "SH_3") (pintype "passive"))
      (node (ref "J11") (pin "4") (pinfunction "SH_4") (pintype "passive"))
      (node (ref "J11") (pin "5") (pinfunction "SH_5") (pintype "passive"))
      (node (ref "J9") (pin "2") (pinfunction "SH_2") (pintype "passive"))
      (node (ref "J9") (pin "3") (pinfunction "SH_3") (pintype "passive"))
      (node (ref "J9") (pin "4") (pinfunction "SH_4") (pintype "passive"))
      (node (ref "J9") (pin "5") (pinfunction "SH_5") (pintype "passive"))
      (node (ref "P13") (pin "10") (pinfunction "10_10") (pintype "passive"))
      (node (ref "P13") (pin "12") (pinfunction "12_12") (pintype "passive"))
      (node (ref "P13") (pin "14") (pinfunction "14_14") (pintype "passive"))
      (node (ref "P13") (pin "16") (pinfunction "16_16") (pintype "passive"))
      (node (ref "P13") (pin "18") (pinfunction "18_18") (pintype "passive"))
      (node (ref "P13") (pin "2") (pinfunction "2_2") (pintype "passive"))
      (node (ref "P13") (pin "20") (pinfunction "20_20") (pintype "passive"))
      (node (ref "P13") (pin "4") (pinfunction "4_4") (pintype "passive"))
      (node (ref "P13") (pin "6") (pinfunction "6_6") (pintype "passive"))
      (node (ref "P13") (pin "8") (pinfunction "8_8") (pintype "passive"))
      (node (ref "P14") (pin "10") (pinfunction "10_10") (pintype "passive"))
      (node (ref "P14") (pin "6") (pinfunction "6_6") (pintype "passive"))
      (node (ref "P14") (pin "7") (pinfunction "7_7") (pintype "passive"))
      (node (ref "P14") (pin "8") (pinfunction "8_8") (pintype "passive"))
      (node (ref "P14") (pin "9") (pinfunction "9_9") (pintype "passive"))
      (node (ref "P15") (pin "10") (pinfunction "10_10") (pintype "passive"))
      (node (ref "P15") (pin "12") (pinfunction "12_12") (pintype "passive"))
      (node (ref "P15") (pin "14") (pinfunction "14_14") (pintype "passive"))
      (node (ref "P15") (pin "16") (pinfunction "16_16") (pintype "passive"))
      (node (ref "P15") (pin "18") (pinfunction "18_18") (pintype "passive"))
      (node (ref "P15") (pin "2") (pinfunction "2_2") (pintype "passive"))
      (node (ref "P15") (pin "20") (pinfunction "20_20") (pintype "passive"))
      (node (ref "P15") (pin "4") (pinfunction "4_4") (pintype "passive"))
      (node (ref "P15") (pin "6") (pinfunction "6_6") (pintype "passive"))
      (node (ref "P15") (pin "8") (pinfunction "8_8") (pintype "passive"))
      (node (ref "R427") (pin "2") (pinfunction "2_2") (pintype "passive"))
      (node (ref "R428") (pin "1") (pinfunction "1_1") (pintype "passive"))
      (node (ref "R429") (pin "1") (pinfunction "1_1") (pintype "passive"))
      (node (ref "R436") (pin "1") (pinfunction "1_1") (pintype "passive"))
      (node (ref "R442") (pin "2") (pinfunction "2_2") (pintype "passive"))
      (node (ref "R443") (pin "1") (pinfunction "1_1") (pintype "passive"))
      (node (ref "R445") (pin "1") (pinfunction "1_1") (pintype "passive"))
      (node (ref "R452") (pin "1") (pinfunction "1_1") (pintype "passive"))
      (node (ref "SP25") (pin "1") (pinfunction "A_1") (pintype "passive"))
      (node (ref "SP26") (pin "1") (pinfunction "A_1") (pintype "passive"))
      (node (ref "SP27") (pin "1") (pinfunction "A_1") (pintype "passive"))
      (node (ref "SP28") (pin "1") (pinfunction "A_1") (pintype "passive"))
      (node (ref "SP29") (pin "1") (pinfunction "A_1") (pintype "passive"))
      (node (ref "SP3") (pin "1") (pinfunction "GND_1") (pintype "power_in"))
      (node (ref "SP30") (pin "1") (pinfunction "A_1") (pintype "passive"))
      (node (ref "SP31") (pin "1") (pinfunction "A_1") (pintype "passive"))
      (node (ref "SP32") (pin "1") (pinfunction "A_1") (pintype "passive"))
      (node (ref "SP33") (pin "1") (pinfunction "A_1") (pintype "passive"))
      (node (ref "SP34") (pin "1") (pinfunction "A_1") (pintype "passive"))
      (node (ref "SP35") (pin "1") (pinfunction "A_1") (pintype "passive"))
      (node (ref "SP36") (pin "1") (pinfunction "A_1") (pintype "passive"))
      (node (ref "SP38") (pin "1") (pinfunction "A_1") (pintype "passive"))
      (node (ref "SP39") (pin "1") (pinfunction "A_1") (pintype "passive"))
      (node (ref "SP40") (pin "1") (pinfunction "A_1") (pintype "passive"))
      (node (ref "SP41") (pin "1") (pinfunction "A_1") (pintype "passive"))
      (node (ref "SP42") (pin "2") (pinfunction "B_2") (pintype "passive"))
      (node (ref "SP43") (pin "1") (pinfunction "A_1") (pintype "passive"))
      (node (ref "SP44") (pin "1") (pinfunction "A_1") (pintype "passive"))
      (node (ref "SP45") (pin "1") (pinfunction "A_1") (pintype "passive"))
      (node (ref "SP46") (pin "1") (pinfunction "A_1") (pintype "passive"))
      (node (ref "U67") (pin "11") (pinfunction "VEE_11") (pintype "power_in"))
      (node (ref "U67") (pin "13") (pinfunction "PAD_13") (pintype "power_in"))
      (node (ref "U67") (pin "3") (pinfunction "VEE_3") (pintype "power_in"))
      (node (ref "U67") (pin "5") (pinfunction "VEE_5") (pintype "power_in"))
      (node (ref "U67") (pin "9") (pinfunction "VEE_9") (pintype "power_in"))
      (node (ref "U68") (pin "11") (pinfunction "GND_11") (pintype "power_in"))
      (node (ref "U68") (pin "12") (pinfunction "GND_12") (pintype "power_in"))
      (node (ref "U68") (pin "13") (pinfunction "GND_13") (pintype "power_in"))
      (node (ref "U69") (pin "11") (pinfunction "VEE_11") (pintype "power_in"))
      (node (ref "U69") (pin "13") (pinfunction "PAD_13") (pintype "power_in"))
      (node (ref "U69") (pin "3") (pinfunction "VEE_3") (pintype "power_in"))
      (node (ref "U69") (pin "5") (pinfunction "VEE_5") (pintype "power_in"))
      (node (ref "U69") (pin "9") (pinfunction "VEE_9") (pintype "power_in"))
      (node (ref "U70") (pin "9") (pinfunction "TH_9") (pintype "passive"))
      (node (ref "U71") (pin "2") (pinfunction "GND_2") (pintype "power_in"))
      (node (ref "U72") (pin "3") (pinfunction "GND_3") (pintype "power_in"))
    )
    (net (code "38") (name "N12V") (class "Default")
      (node (ref "C485") (pin "2") (pinfunction "2_2") (pintype "passive"))
      (node (ref "U70") (pin "4") (pinfunction "VS-_4") (pintype "power_in"))
    )
    (net (code "39") (name "Net-(DS15-A)") (class "Default")
      (node (ref "DS15") (pin "2") (pinfunction "A_2") (pintype "passive"))
      (node (ref "R423") (pin "1") (pinfunction "1_1") (pintype "passive"))
    )
    (net (code "40") (name "Net-(DS16-A)") (class "Default")
      (node (ref "DS16") (pin "2") (pinfunction "A_2") (pintype "passive"))
      (node (ref "R422") (pin "1") (pinfunction "1_1") (pintype "passive"))
    )
    (net (code "41") (name "Net-(DS17-A)") (class "Default")
      (node (ref "DS17") (pin "2") (pinfunction "A_2") (pintype "passive"))
      (node (ref "R424") (pin "1") (pinfunction "1_1") (pintype "passive"))
    )
    (net (code "42") (name "Net-(DS18-A)") (class "Default")
      (node (ref "DS18") (pin "2") (pinfunction "A_2") (pintype "passive"))
      (node (ref "R425") (pin "1") (pinfunction "1_1") (pintype "passive"))
    )
    (net (code "43") (name "Net-(DS19-A)") (class "Default")
      (node (ref "DS19") (pin "2") (pinfunction "A_2") (pintype "passive"))
      (node (ref "R432") (pin "2") (pinfunction "2_2") (pintype "passive"))
    )
    (net (code "44") (name "Net-(DS20-A)") (class "Default")
      (node (ref "DS20") (pin "2") (pinfunction "A_2") (pintype "passive"))
      (node (ref "R433") (pin "2") (pinfunction "2_2") (pintype "passive"))
    )
    (net (code "45") (name "Net-(DS21-A)") (class "Default")
      (node (ref "DS21") (pin "2") (pinfunction "A_2") (pintype "passive"))
      (node (ref "R434") (pin "2") (pinfunction "2_2") (pintype "passive"))
    )
    (net (code "46") (name "Net-(DS22-A)") (class "Default")
      (node (ref "DS22") (pin "2") (pinfunction "A_2") (pintype "passive"))
      (node (ref "R431") (pin "2") (pinfunction "2_2") (pintype "passive"))
    )
    (net (code "47") (name "Net-(F5-Pad2)") (class "Default")
      (node (ref "F5") (pin "2") (pinfunction "2_2") (pintype "passive"))
      (node (ref "P13") (pin "19") (pinfunction "19_19") (pintype "passive"))
      (node (ref "P15") (pin "19") (pinfunction "19_19") (pintype "passive"))
    )
    (net (code "48") (name "Net-(F8-Pad2)") (class "Default")
      (node (ref "F8") (pin "2") (pinfunction "2_2") (pintype "passive"))
      (node (ref "P13") (pin "1") (pinfunction "1_1") (pintype "passive"))
      (node (ref "P15") (pin "1") (pinfunction "1_1") (pintype "passive"))
    )
    (net (code "49") (name "Net-(F9-Pad1)") (class "Default")
      (node (ref "F9") (pin "1") (pinfunction "1_1") (pintype "passive"))
      (node (ref "P14") (pin "1") (pinfunction "1_1") (pintype "passive"))
    )
    (net (code "50") (name "Net-(J9-IN)") (class "Default")
      (node (ref "C720") (pin "2") (pinfunction "2_2") (pintype "passive"))
      (node (ref "J9") (pin "1") (pinfunction "IN_1") (pintype "passive"))
      (node (ref "R426") (pin "1") (pinfunction "1_1") (pintype "passive"))
      (node (ref "SP3") (pin "3") (pinfunction "IO2_3") (pintype "power_in"))
    )
    (net (code "51") (name "Net-(J10-IN)") (class "Default")
      (node (ref "C724") (pin "2") (pinfunction "2_2") (pintype "passive"))
      (node (ref "J10") (pin "1") (pinfunction "IN_1") (pintype "passive"))
      (node (ref "R441") (pin "1") (pinfunction "1_1") (pintype "passive"))
      (node (ref "SP3") (pin "2") (pinfunction "IO1_2") (pintype "power_in"))
    )
    (net (code "52") (name "Net-(J11-IN)") (class "Default")
      (node (ref "J11") (pin "1") (pinfunction "IN_1") (pintype "passive"))
      (node (ref "R447") (pin "2") (pinfunction "2_2") (pintype "passive"))
      (node (ref "SP42") (pin "1") (pinfunction "A_1") (pintype "passive"))
    )
    (net (code "53") (name "Net-(U67-LE{slash}HYS)") (class "Default")
      (node (ref "R429") (pin "2") (pinfunction "2_2") (pintype "passive"))
      (node (ref "U67") (pin "8") (pinfunction "LE/HYS_8") (pintype "input"))
    )
    (net (code "54") (name "Net-(U67-SDN)") (class "Default")
      (node (ref "R419") (pin "1") (pinfunction "1_1") (pintype "passive"))
      (node (ref "U67") (pin "7") (pinfunction "SDN_7") (pintype "input"))
    )
    (net (code "55") (name "Net-(U67-VN)") (class "Default")
      (node (ref "C721") (pin "2") (pinfunction "2_2") (pintype "passive"))
      (node (ref "R421") (pin "1") (pinfunction "1_1") (pintype "passive"))
      (node (ref "R428") (pin "2") (pinfunction "2_2") (pintype "passive"))
      (node (ref "U67") (pin "6") (pinfunction "VN_6") (pintype "input"))
    )
    (net (code "56") (name "Net-(U67-VP)") (class "Default")
      (node (ref "C720") (pin "1") (pinfunction "1_1") (pintype "passive"))
      (node (ref "R420") (pin "2") (pinfunction "2_2") (pintype "passive"))
      (node (ref "R426") (pin "2") (pinfunction "2_2") (pintype "passive"))
      (node (ref "R427") (pin "1") (pinfunction "1_1") (pintype "passive"))
      (node (ref "U67") (pin "4") (pinfunction "VP_4") (pintype "input"))
    )
    (net (code "57") (name "Net-(U68-B1)") (class "Default")
      (node (ref "R431") (pin "1") (pinfunction "1_1") (pintype "passive"))
      (node (ref "U68") (pin "21") (pinfunction "B1_21") (pintype "bidirectional"))
    )
    (net (code "58") (name "Net-(U68-B2)") (class "Default")
      (node (ref "R432") (pin "1") (pinfunction "1_1") (pintype "passive"))
      (node (ref "U68") (pin "20") (pinfunction "B2_20") (pintype "bidirectional"))
    )
    (net (code "59") (name "Net-(U68-B3)") (class "Default")
      (node (ref "R433") (pin "1") (pinfunction "1_1") (pintype "passive"))
      (node (ref "U68") (pin "19") (pinfunction "B3_19") (pintype "bidirectional"))
    )
    (net (code "60") (name "Net-(U68-B4)") (class "Default")
      (node (ref "R434") (pin "1") (pinfunction "1_1") (pintype "passive"))
      (node (ref "U68") (pin "18") (pinfunction "B4_18") (pintype "bidirectional"))
    )
    (net (code "61") (name "Net-(U68-B5)") (class "Default")
      (node (ref "R425") (pin "2") (pinfunction "2_2") (pintype "passive"))
      (node (ref "U68") (pin "17") (pinfunction "B5_17") (pintype "bidirectional"))
    )
    (net (code "62") (name "Net-(U68-B6)") (class "Default")
      (node (ref "R424") (pin "2") (pinfunction "2_2") (pintype "passive"))
      (node (ref "U68") (pin "16") (pinfunction "B6_16") (pintype "bidirectional"))
    )
    (net (code "63") (name "Net-(U68-B7)") (class "Default")
      (node (ref "R422") (pin "2") (pinfunction "2_2") (pintype "passive"))
      (node (ref "U68") (pin "15") (pinfunction "B7_15") (pintype "bidirectional"))
    )
    (net (code "64") (name "Net-(U68-B8)") (class "Default")
      (node (ref "R423") (pin "2") (pinfunction "2_2") (pintype "passive"))
      (node (ref "U68") (pin "14") (pinfunction "B8_14") (pintype "bidirectional"))
    )
    (net (code "65") (name "Net-(U68-DIR)") (class "Default")
      (node (ref "R435") (pin "1") (pinfunction "1_1") (pintype "passive"))
      (node (ref "U68") (pin "2") (pinfunction "DIR_2") (pintype "bidirectional"))
    )
    (net (code "66") (name "Net-(U68-OEn)") (class "Default")
      (node (ref "R430") (pin "1") (pinfunction "1_1") (pintype "passive"))
      (node (ref "R436") (pin "2") (pinfunction "2_2") (pintype "passive"))
      (node (ref "U68") (pin "22") (pinfunction "OEn_22") (pintype "bidirectional"))
    )
    (net (code "67") (name "Net-(U69-LE{slash}HYS)") (class "Default")
      (node (ref "R445") (pin "2") (pinfunction "2_2") (pintype "passive"))
      (node (ref "U69") (pin "8") (pinfunction "LE/HYS_8") (pintype "input"))
    )
    (net (code "68") (name "Net-(U69-SDN)") (class "Default")
      (node (ref "R438") (pin "1") (pinfunction "1_1") (pintype "passive"))
      (node (ref "U69") (pin "7") (pinfunction "SDN_7") (pintype "input"))
    )
    (net (code "69") (name "Net-(U69-VN)") (class "Default")
      (node (ref "C725") (pin "2") (pinfunction "2_2") (pintype "passive"))
      (node (ref "R440") (pin "1") (pinfunction "1_1") (pintype "passive"))
      (node (ref "R443") (pin "2") (pinfunction "2_2") (pintype "passive"))
      (node (ref "U69") (pin "6") (pinfunction "VN_6") (pintype "input"))
    )
    (net (code "70") (name "Net-(U69-VP)") (class "Default")
      (node (ref "C724") (pin "1") (pinfunction "1_1") (pintype "passive"))
      (node (ref "R439") (pin "2") (pinfunction "2_2") (pintype "passive"))
      (node (ref "R441") (pin "2") (pinfunction "2_2") (pintype "passive"))
      (node (ref "R442") (pin "1") (pinfunction "1_1") (pintype "passive"))
      (node (ref "U69") (pin "4") (pinfunction "VP_4") (pintype "input"))
    )
    (net (code "71") (name "Net-(U70-VIN+)") (class "Default")
      (node (ref "U70") (pin "3") (pinfunction "VIN+_3") (pintype "input"))
      (node (ref "U71") (pin "5") (pinfunction "R_5") (pintype "output"))
    )
    (net (code "72") (name "Net-(U70-VIN-)") (class "Default")
      (node (ref "C726") (pin "2") (pinfunction "2_2") (pintype "passive"))
      (node (ref "R450") (pin "1") (pinfunction "1_1") (pintype "passive"))
      (node (ref "R452") (pin "2") (pinfunction "2_2") (pintype "passive"))
      (node (ref "U70") (pin "2") (pinfunction "VIN-_2") (pintype "input"))
    )
    (net (code "73") (name "Net-(U70-VOUT)") (class "Default")
      (node (ref "R447") (pin "1") (pinfunction "1_1") (pintype "passive"))
      (node (ref "R450") (pin "2") (pinfunction "2_2") (pintype "passive"))
      (node (ref "U70") (pin "6") (pinfunction "VOUT_6") (pintype "output"))
    )
    (net (code "74") (name "unconnected-(U70-NC-Pad1)") (class "Default")
      (node (ref "U70") (pin "1") (pinfunction "NC_1") (pintype "passive+no_connect"))
    )
    (net (code "75") (name "unconnected-(U70-NC-Pad5)") (class "Default")
      (node (ref "U70") (pin "5") (pinfunction "NC_5") (pintype "passive+no_connect"))
    )
    (net (code "76") (name "unconnected-(U70-NC-Pad8)") (class "Default")
      (node (ref "U70") (pin "8") (pinfunction "NC_8") (pintype "passive+no_connect"))
    )
    (net (code "77") (name "unconnected-(U72-E{slash}D-Pad1)") (class "Default")
      (node (ref "U72") (pin "1") (pinfunction "E/D_1") (pintype "input+no_connect"))
    )
    (net (code "78") (name "unconnected-(U72-NC-Pad2)") (class "Default")
      (node (ref "U72") (pin "2") (pinfunction "NC_2") (pintype "passive+no_connect"))
    )
  )
)
